# dual-dac-w-32-ch-sh-SH-BOARD_v2.net
KiCad netlist of a schematic drawn in EAGLE
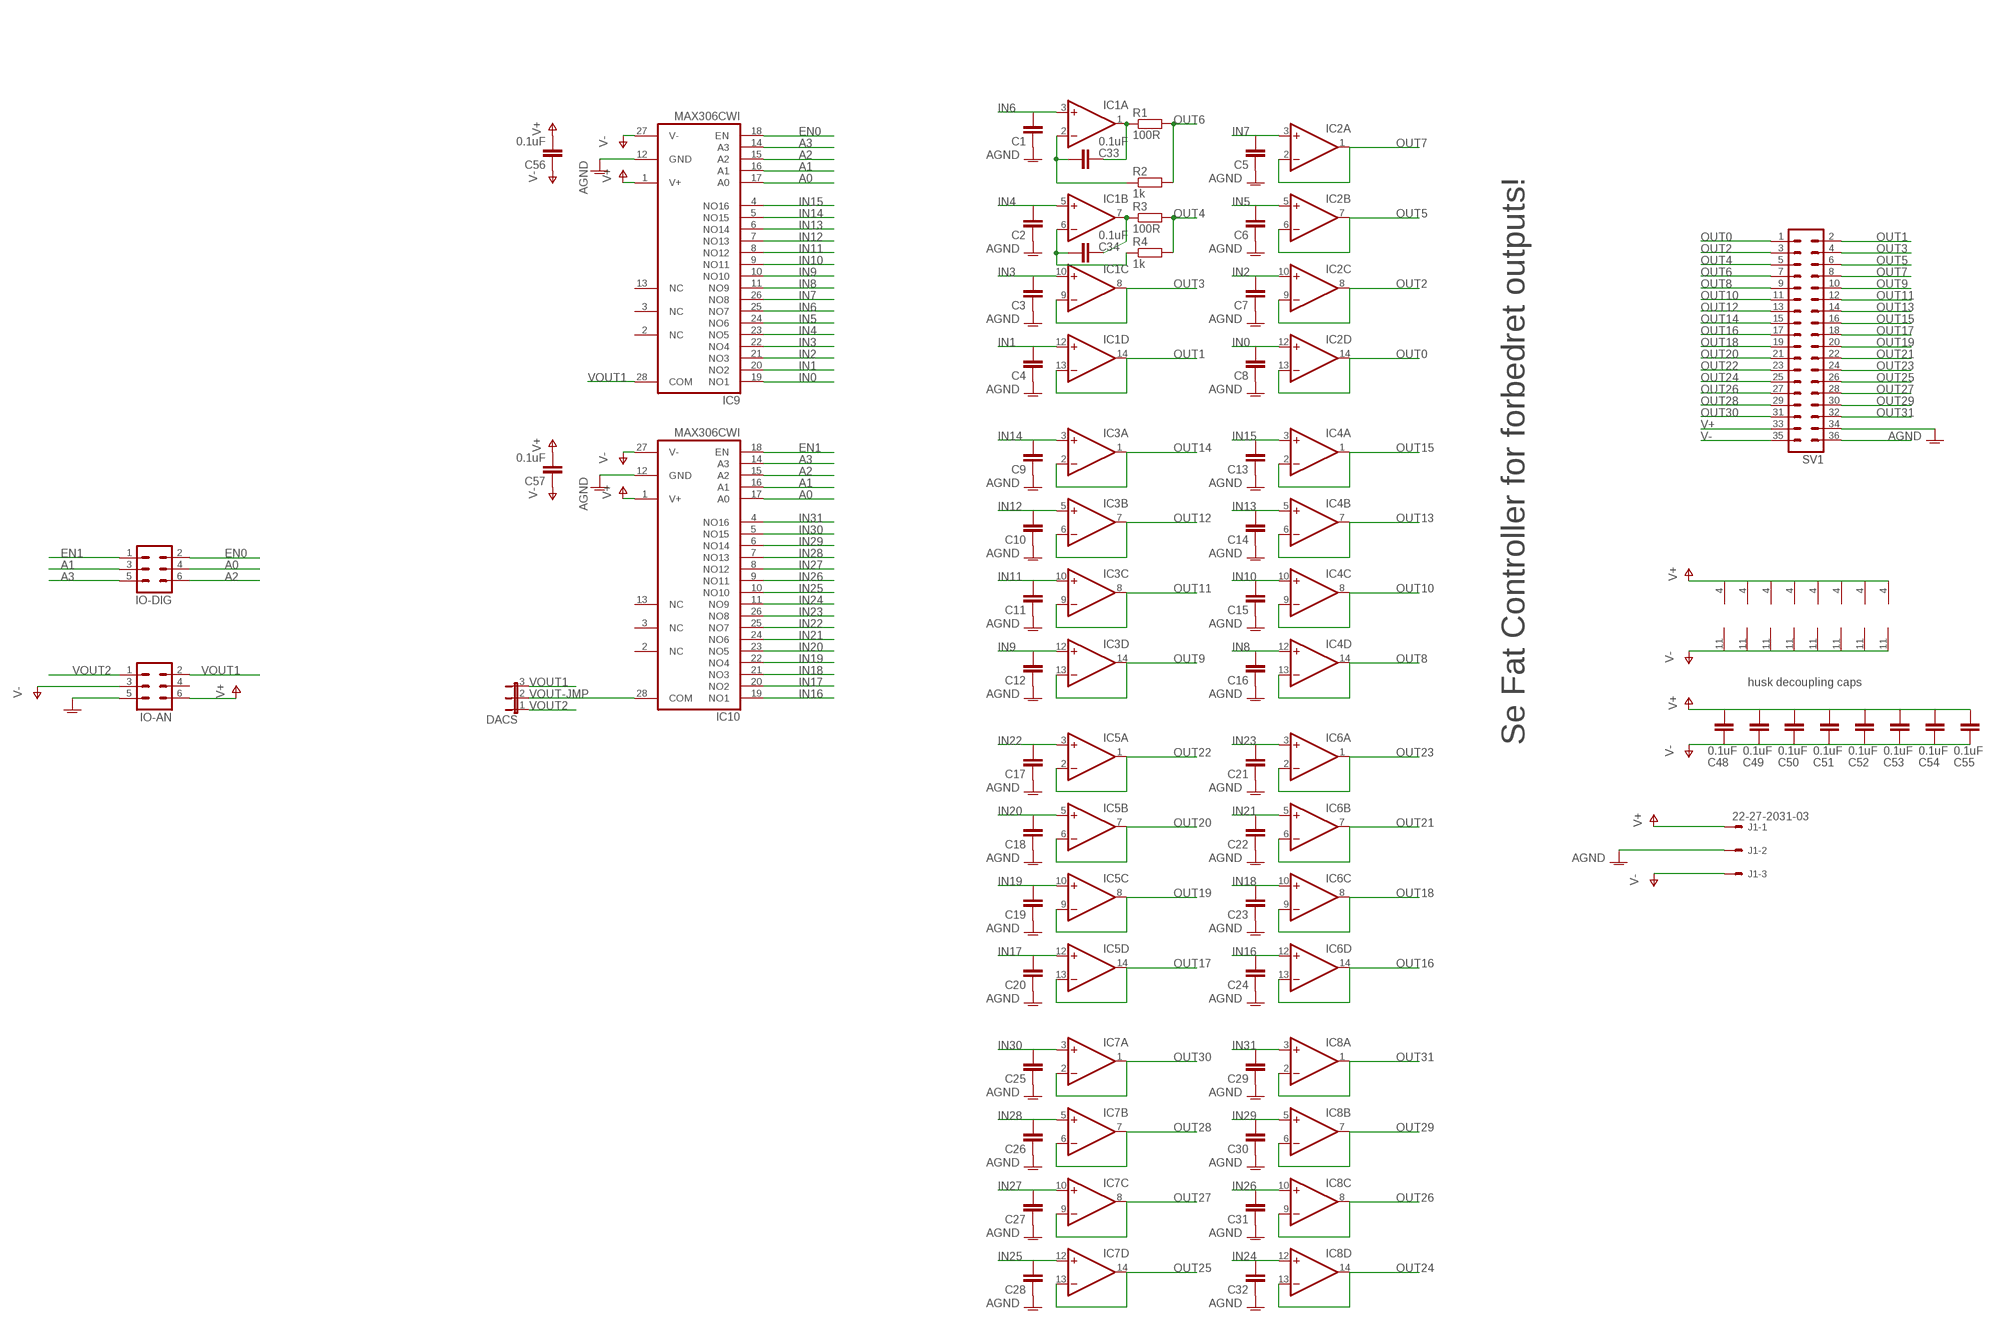
[diagram p0: schematic, sheet 1]

(export (version "E")
  (design (tool "Eeschema 10.0.6"))
  (components
    (comp (ref "C1")
      (value "C-EUC1206")
      (footprint "eagle-import:C1206")
      (libsource (lib "eagle-import") (part "C-EUC1206"))
    )
    (comp (ref "C2")
      (value "C-EUC1206")
      (footprint "eagle-import:C1206")
      (libsource (lib "eagle-import") (part "C-EUC1206"))
    )
    (comp (ref "C3")
      (value "C-EUC1206")
      (footprint "eagle-import:C1206")
      (libsource (lib "eagle-import") (part "C-EUC1206"))
    )
    (comp (ref "C4")
      (value "C-EUC1206")
      (footprint "eagle-import:C1206")
      (libsource (lib "eagle-import") (part "C-EUC1206"))
    )
    (comp (ref "C5")
      (value "C-EUC1206")
      (footprint "eagle-import:C1206")
      (libsource (lib "eagle-import") (part "C-EUC1206"))
    )
    (comp (ref "C6")
      (value "C-EUC1206")
      (footprint "eagle-import:C1206")
      (libsource (lib "eagle-import") (part "C-EUC1206"))
    )
    (comp (ref "C7")
      (value "C-EUC1206")
      (footprint "eagle-import:C1206")
      (libsource (lib "eagle-import") (part "C-EUC1206"))
    )
    (comp (ref "C8")
      (value "C-EUC1206")
      (footprint "eagle-import:C1206")
      (libsource (lib "eagle-import") (part "C-EUC1206"))
    )
    (comp (ref "C9")
      (value "C-EUC1206")
      (footprint "eagle-import:C1206")
      (libsource (lib "eagle-import") (part "C-EUC1206"))
    )
    (comp (ref "C10")
      (value "C-EUC1206")
      (footprint "eagle-import:C1206")
      (libsource (lib "eagle-import") (part "C-EUC1206"))
    )
    (comp (ref "C11")
      (value "C-EUC1206")
      (footprint "eagle-import:C1206")
      (libsource (lib "eagle-import") (part "C-EUC1206"))
    )
    (comp (ref "C12")
      (value "C-EUC1206")
      (footprint "eagle-import:C1206")
      (libsource (lib "eagle-import") (part "C-EUC1206"))
    )
    (comp (ref "C13")
      (value "C-EUC1206")
      (footprint "eagle-import:C1206")
      (libsource (lib "eagle-import") (part "C-EUC1206"))
    )
    (comp (ref "C14")
      (value "C-EUC1206")
      (footprint "eagle-import:C1206")
      (libsource (lib "eagle-import") (part "C-EUC1206"))
    )
    (comp (ref "C15")
      (value "C-EUC1206")
      (footprint "eagle-import:C1206")
      (libsource (lib "eagle-import") (part "C-EUC1206"))
    )
    (comp (ref "C16")
      (value "C-EUC1206")
      (footprint "eagle-import:C1206")
      (libsource (lib "eagle-import") (part "C-EUC1206"))
    )
    (comp (ref "C17")
      (value "C-EUC1206")
      (footprint "eagle-import:C1206")
      (libsource (lib "eagle-import") (part "C-EUC1206"))
    )
    (comp (ref "C18")
      (value "C-EUC1206")
      (footprint "eagle-import:C1206")
      (libsource (lib "eagle-import") (part "C-EUC1206"))
    )
    (comp (ref "C19")
      (value "C-EUC1206")
      (footprint "eagle-import:C1206")
      (libsource (lib "eagle-import") (part "C-EUC1206"))
    )
    (comp (ref "C20")
      (value "C-EUC1206")
      (footprint "eagle-import:C1206")
      (libsource (lib "eagle-import") (part "C-EUC1206"))
    )
    (comp (ref "C21")
      (value "C-EUC1206")
      (footprint "eagle-import:C1206")
      (libsource (lib "eagle-import") (part "C-EUC1206"))
    )
    (comp (ref "C22")
      (value "C-EUC1206")
      (footprint "eagle-import:C1206")
      (libsource (lib "eagle-import") (part "C-EUC1206"))
    )
    (comp (ref "C23")
      (value "C-EUC1206")
      (footprint "eagle-import:C1206")
      (libsource (lib "eagle-import") (part "C-EUC1206"))
    )
    (comp (ref "C24")
      (value "C-EUC1206")
      (footprint "eagle-import:C1206")
      (libsource (lib "eagle-import") (part "C-EUC1206"))
    )
    (comp (ref "C25")
      (value "C-EUC1206")
      (footprint "eagle-import:C1206")
      (libsource (lib "eagle-import") (part "C-EUC1206"))
    )
    (comp (ref "C26")
      (value "C-EUC1206")
      (footprint "eagle-import:C1206")
      (libsource (lib "eagle-import") (part "C-EUC1206"))
    )
    (comp (ref "C27")
      (value "C-EUC1206")
      (footprint "eagle-import:C1206")
      (libsource (lib "eagle-import") (part "C-EUC1206"))
    )
    (comp (ref "C28")
      (value "C-EUC1206")
      (footprint "eagle-import:C1206")
      (libsource (lib "eagle-import") (part "C-EUC1206"))
    )
    (comp (ref "C29")
      (value "C-EUC1206")
      (footprint "eagle-import:C1206")
      (libsource (lib "eagle-import") (part "C-EUC1206"))
    )
    (comp (ref "C30")
      (value "C-EUC1206")
      (footprint "eagle-import:C1206")
      (libsource (lib "eagle-import") (part "C-EUC1206"))
    )
    (comp (ref "C31")
      (value "C-EUC1206")
      (footprint "eagle-import:C1206")
      (libsource (lib "eagle-import") (part "C-EUC1206"))
    )
    (comp (ref "C32")
      (value "C-EUC1206")
      (footprint "eagle-import:C1206")
      (libsource (lib "eagle-import") (part "C-EUC1206"))
    )
    (comp (ref "C33")
      (value "0.1uF")
      (footprint "eagle-import:C0603")
      (libsource (lib "eagle-import") (part "C-EUC0603"))
    )
    (comp (ref "C34")
      (value "0.1uF")
      (footprint "eagle-import:C0603")
      (libsource (lib "eagle-import") (part "C-EUC0603"))
    )
    (comp (ref "C48")
      (value "0.1uF")
      (footprint "eagle-import:C0603")
      (libsource (lib "eagle-import") (part "C-EUC0603"))
    )
    (comp (ref "C49")
      (value "0.1uF")
      (footprint "eagle-import:C0603")
      (libsource (lib "eagle-import") (part "C-EUC0603"))
    )
    (comp (ref "C50")
      (value "0.1uF")
      (footprint "eagle-import:C0603")
      (libsource (lib "eagle-import") (part "C-EUC0603"))
    )
    (comp (ref "C51")
      (value "0.1uF")
      (footprint "eagle-import:C0603")
      (libsource (lib "eagle-import") (part "C-EUC0603"))
    )
    (comp (ref "C52")
      (value "0.1uF")
      (footprint "eagle-import:C0603")
      (libsource (lib "eagle-import") (part "C-EUC0603"))
    )
    (comp (ref "C53")
      (value "0.1uF")
      (footprint "eagle-import:C0603")
      (libsource (lib "eagle-import") (part "C-EUC0603"))
    )
    (comp (ref "C54")
      (value "0.1uF")
      (footprint "eagle-import:C0603")
      (libsource (lib "eagle-import") (part "C-EUC0603"))
    )
    (comp (ref "C55")
      (value "0.1uF")
      (footprint "eagle-import:C0603")
      (libsource (lib "eagle-import") (part "C-EUC0603"))
    )
    (comp (ref "C56")
      (value "0.1uF")
      (footprint "eagle-import:C0603")
      (libsource (lib "eagle-import") (part "C-EUC0603"))
    )
    (comp (ref "C57")
      (value "0.1uF")
      (footprint "eagle-import:C0603")
      (libsource (lib "eagle-import") (part "C-EUC0603"))
    )
    (comp (ref "DACS")
      (value "JP2E")
      (footprint "eagle-import:JP2")
      (libsource (lib "eagle-import") (part "JP2E"))
    )
    (comp (ref "IC1")
      (value "TL074D")
      (footprint "eagle-import:SO14")
      (libsource (lib "eagle-import") (part "TL074D"))
    )
    (comp (ref "IC2")
      (value "TL074D")
      (footprint "eagle-import:SO14")
      (libsource (lib "eagle-import") (part "TL074D"))
    )
    (comp (ref "IC3")
      (value "TL074D")
      (footprint "eagle-import:SO14")
      (libsource (lib "eagle-import") (part "TL074D"))
    )
    (comp (ref "IC4")
      (value "TL074D")
      (footprint "eagle-import:SO14")
      (libsource (lib "eagle-import") (part "TL074D"))
    )
    (comp (ref "IC5")
      (value "TL074D")
      (footprint "eagle-import:SO14")
      (libsource (lib "eagle-import") (part "TL074D"))
    )
    (comp (ref "IC6")
      (value "TL074D")
      (footprint "eagle-import:SO14")
      (libsource (lib "eagle-import") (part "TL074D"))
    )
    (comp (ref "IC7")
      (value "TL074D")
      (footprint "eagle-import:SO14")
      (libsource (lib "eagle-import") (part "TL074D"))
    )
    (comp (ref "IC8")
      (value "TL074D")
      (footprint "eagle-import:SO14")
      (libsource (lib "eagle-import") (part "TL074D"))
    )
    (comp (ref "IC9")
      (value "MAX306CWI")
      (footprint "eagle-import:SO28L")
      (fields (field (name "MF") "MAXIM"))
      (libsource (lib "eagle-import") (part "MAX306CWI"))
    )
    (comp (ref "IC10")
      (value "MAX306CWI")
      (footprint "eagle-import:SO28L")
      (fields (field (name "MF") "MAXIM"))
      (libsource (lib "eagle-import") (part "MAX306CWI"))
    )
    (comp (ref "IO-AN")
      (value "MA03-2")
      (footprint "eagle-import:MA03-2")
      (libsource (lib "eagle-import") (part "MA03-2"))
    )
    (comp (ref "IO-DIG")
      (value "MA03-2")
      (footprint "eagle-import:MA03-2")
      (libsource (lib "eagle-import") (part "MA03-2"))
    )
    (comp (ref "J1")
      (value "22-27-2031-03")
      (footprint "eagle-import:6410-03")
      (libsource (lib "eagle-import") (part "22-?-0327-2031"))
    )
    (comp (ref "R1")
      (value "100R")
      (footprint "eagle-import:R0603")
      (libsource (lib "eagle-import") (part "R-EU_R0603"))
    )
    (comp (ref "R2")
      (value "1k")
      (footprint "eagle-import:R0603")
      (libsource (lib "eagle-import") (part "R-EU_R0603"))
    )
    (comp (ref "R3")
      (value "100R")
      (footprint "eagle-import:R0603")
      (libsource (lib "eagle-import") (part "R-EU_R0603"))
    )
    (comp (ref "R4")
      (value "1k")
      (footprint "eagle-import:R0603")
      (libsource (lib "eagle-import") (part "R-EU_R0603"))
    )
    (comp (ref "SV1")
      (value "MA18-2")
      (footprint "eagle-import:MA18-2")
      (libsource (lib "eagle-import") (part "MA18-2"))
    )
  )
  (nets
    (net (code "1") (name "/A0") (class "Default")
      (node (ref "IC10") (pin "17") (pinfunction "A0_17") (pintype "input"))
      (node (ref "IC9") (pin "17") (pinfunction "A0_17") (pintype "input"))
      (node (ref "IO-DIG") (pin "4") (pinfunction "4_4") (pintype "passive"))
    )
    (net (code "2") (name "/A1") (class "Default")
      (node (ref "IC10") (pin "16") (pinfunction "A1_16") (pintype "input"))
      (node (ref "IC9") (pin "16") (pinfunction "A1_16") (pintype "input"))
      (node (ref "IO-DIG") (pin "3") (pinfunction "3_3") (pintype "passive"))
    )
    (net (code "3") (name "/A2") (class "Default")
      (node (ref "IC10") (pin "15") (pinfunction "A2_15") (pintype "input"))
      (node (ref "IC9") (pin "15") (pinfunction "A2_15") (pintype "input"))
      (node (ref "IO-DIG") (pin "6") (pinfunction "6_6") (pintype "passive"))
    )
    (net (code "4") (name "/A3") (class "Default")
      (node (ref "IC10") (pin "14") (pinfunction "A3_14") (pintype "input"))
      (node (ref "IC9") (pin "14") (pinfunction "A3_14") (pintype "input"))
      (node (ref "IO-DIG") (pin "5") (pinfunction "5_5") (pintype "passive"))
    )
    (net (code "5") (name "/EN0") (class "Default")
      (node (ref "IC9") (pin "18") (pinfunction "EN_18") (pintype "input"))
      (node (ref "IO-DIG") (pin "2") (pinfunction "2_2") (pintype "passive"))
    )
    (net (code "6") (name "/EN1") (class "Default")
      (node (ref "IC10") (pin "18") (pinfunction "EN_18") (pintype "input"))
      (node (ref "IO-DIG") (pin "1") (pinfunction "1_1") (pintype "passive"))
    )
    (net (code "7") (name "/IN0") (class "Default")
      (node (ref "C8") (pin "2") (pinfunction "2_2") (pintype "passive"))
      (node (ref "IC2") (pin "12") (pinfunction "+IN_12") (pintype "input"))
      (node (ref "IC9") (pin "19") (pinfunction "NO1_19") (pintype "passive"))
    )
    (net (code "8") (name "/IN1") (class "Default")
      (node (ref "C4") (pin "2") (pinfunction "2_2") (pintype "passive"))
      (node (ref "IC1") (pin "12") (pinfunction "+IN_12") (pintype "input"))
      (node (ref "IC9") (pin "20") (pinfunction "NO2_20") (pintype "passive"))
    )
    (net (code "9") (name "/IN2") (class "Default")
      (node (ref "C7") (pin "2") (pinfunction "2_2") (pintype "passive"))
      (node (ref "IC2") (pin "10") (pinfunction "+IN_10") (pintype "input"))
      (node (ref "IC9") (pin "21") (pinfunction "NO3_21") (pintype "passive"))
    )
    (net (code "10") (name "/IN3") (class "Default")
      (node (ref "C3") (pin "2") (pinfunction "2_2") (pintype "passive"))
      (node (ref "IC1") (pin "10") (pinfunction "+IN_10") (pintype "input"))
      (node (ref "IC9") (pin "22") (pinfunction "NO4_22") (pintype "passive"))
    )
    (net (code "11") (name "/IN4") (class "Default")
      (node (ref "C2") (pin "2") (pinfunction "2_2") (pintype "passive"))
      (node (ref "IC1") (pin "5") (pinfunction "+IN_5") (pintype "input"))
      (node (ref "IC9") (pin "23") (pinfunction "NO5_23") (pintype "passive"))
    )
    (net (code "12") (name "/IN5") (class "Default")
      (node (ref "C6") (pin "2") (pinfunction "2_2") (pintype "passive"))
      (node (ref "IC2") (pin "5") (pinfunction "+IN_5") (pintype "input"))
      (node (ref "IC9") (pin "24") (pinfunction "NO6_24") (pintype "passive"))
    )
    (net (code "13") (name "/IN6") (class "Default")
      (node (ref "C1") (pin "2") (pinfunction "2_2") (pintype "passive"))
      (node (ref "IC1") (pin "3") (pinfunction "+IN_3") (pintype "input"))
      (node (ref "IC9") (pin "25") (pinfunction "NO7_25") (pintype "passive"))
    )
    (net (code "14") (name "/IN7") (class "Default")
      (node (ref "C5") (pin "2") (pinfunction "2_2") (pintype "passive"))
      (node (ref "IC2") (pin "3") (pinfunction "+IN_3") (pintype "input"))
      (node (ref "IC9") (pin "26") (pinfunction "NO8_26") (pintype "passive"))
    )
    (net (code "15") (name "/IN8") (class "Default")
      (node (ref "C16") (pin "2") (pinfunction "2_2") (pintype "passive"))
      (node (ref "IC4") (pin "12") (pinfunction "+IN_12") (pintype "input"))
      (node (ref "IC9") (pin "11") (pinfunction "NO9_11") (pintype "passive"))
    )
    (net (code "16") (name "/IN9") (class "Default")
      (node (ref "C12") (pin "2") (pinfunction "2_2") (pintype "passive"))
      (node (ref "IC3") (pin "12") (pinfunction "+IN_12") (pintype "input"))
      (node (ref "IC9") (pin "10") (pinfunction "NO10_10") (pintype "passive"))
    )
    (net (code "17") (name "/IN10") (class "Default")
      (node (ref "C15") (pin "2") (pinfunction "2_2") (pintype "passive"))
      (node (ref "IC4") (pin "10") (pinfunction "+IN_10") (pintype "input"))
      (node (ref "IC9") (pin "9") (pinfunction "NO11_9") (pintype "passive"))
    )
    (net (code "18") (name "/IN11") (class "Default")
      (node (ref "C11") (pin "2") (pinfunction "2_2") (pintype "passive"))
      (node (ref "IC3") (pin "10") (pinfunction "+IN_10") (pintype "input"))
      (node (ref "IC9") (pin "8") (pinfunction "NO12_8") (pintype "passive"))
    )
    (net (code "19") (name "/IN12") (class "Default")
      (node (ref "C10") (pin "2") (pinfunction "2_2") (pintype "passive"))
      (node (ref "IC3") (pin "5") (pinfunction "+IN_5") (pintype "input"))
      (node (ref "IC9") (pin "7") (pinfunction "NO13_7") (pintype "passive"))
    )
    (net (code "20") (name "/IN13") (class "Default")
      (node (ref "C14") (pin "2") (pinfunction "2_2") (pintype "passive"))
      (node (ref "IC4") (pin "5") (pinfunction "+IN_5") (pintype "input"))
      (node (ref "IC9") (pin "6") (pinfunction "NO14_6") (pintype "passive"))
    )
    (net (code "21") (name "/IN14") (class "Default")
      (node (ref "C9") (pin "2") (pinfunction "2_2") (pintype "passive"))
      (node (ref "IC3") (pin "3") (pinfunction "+IN_3") (pintype "input"))
      (node (ref "IC9") (pin "5") (pinfunction "NO15_5") (pintype "passive"))
    )
    (net (code "22") (name "/IN15") (class "Default")
      (node (ref "C13") (pin "2") (pinfunction "2_2") (pintype "passive"))
      (node (ref "IC4") (pin "3") (pinfunction "+IN_3") (pintype "input"))
      (node (ref "IC9") (pin "4") (pinfunction "NO16_4") (pintype "passive"))
    )
    (net (code "23") (name "/IN16") (class "Default")
      (node (ref "C24") (pin "2") (pinfunction "2_2") (pintype "passive"))
      (node (ref "IC10") (pin "19") (pinfunction "NO1_19") (pintype "passive"))
      (node (ref "IC6") (pin "12") (pinfunction "+IN_12") (pintype "input"))
    )
    (net (code "24") (name "/IN17") (class "Default")
      (node (ref "C20") (pin "2") (pinfunction "2_2") (pintype "passive"))
      (node (ref "IC10") (pin "20") (pinfunction "NO2_20") (pintype "passive"))
      (node (ref "IC5") (pin "12") (pinfunction "+IN_12") (pintype "input"))
    )
    (net (code "25") (name "/IN18") (class "Default")
      (node (ref "C23") (pin "2") (pinfunction "2_2") (pintype "passive"))
      (node (ref "IC10") (pin "21") (pinfunction "NO3_21") (pintype "passive"))
      (node (ref "IC6") (pin "10") (pinfunction "+IN_10") (pintype "input"))
    )
    (net (code "26") (name "/IN19") (class "Default")
      (node (ref "C19") (pin "2") (pinfunction "2_2") (pintype "passive"))
      (node (ref "IC10") (pin "22") (pinfunction "NO4_22") (pintype "passive"))
      (node (ref "IC5") (pin "10") (pinfunction "+IN_10") (pintype "input"))
    )
    (net (code "27") (name "/IN20") (class "Default")
      (node (ref "C18") (pin "2") (pinfunction "2_2") (pintype "passive"))
      (node (ref "IC10") (pin "23") (pinfunction "NO5_23") (pintype "passive"))
      (node (ref "IC5") (pin "5") (pinfunction "+IN_5") (pintype "input"))
    )
    (net (code "28") (name "/IN21") (class "Default")
      (node (ref "C22") (pin "2") (pinfunction "2_2") (pintype "passive"))
      (node (ref "IC10") (pin "24") (pinfunction "NO6_24") (pintype "passive"))
      (node (ref "IC6") (pin "5") (pinfunction "+IN_5") (pintype "input"))
    )
    (net (code "29") (name "/IN22") (class "Default")
      (node (ref "C17") (pin "2") (pinfunction "2_2") (pintype "passive"))
      (node (ref "IC10") (pin "25") (pinfunction "NO7_25") (pintype "passive"))
      (node (ref "IC5") (pin "3") (pinfunction "+IN_3") (pintype "input"))
    )
    (net (code "30") (name "/IN23") (class "Default")
      (node (ref "C21") (pin "2") (pinfunction "2_2") (pintype "passive"))
      (node (ref "IC10") (pin "26") (pinfunction "NO8_26") (pintype "passive"))
      (node (ref "IC6") (pin "3") (pinfunction "+IN_3") (pintype "input"))
    )
    (net (code "31") (name "/IN24") (class "Default")
      (node (ref "C32") (pin "2") (pinfunction "2_2") (pintype "passive"))
      (node (ref "IC10") (pin "11") (pinfunction "NO9_11") (pintype "passive"))
      (node (ref "IC8") (pin "12") (pinfunction "+IN_12") (pintype "input"))
    )
    (net (code "32") (name "/IN25") (class "Default")
      (node (ref "C28") (pin "2") (pinfunction "2_2") (pintype "passive"))
      (node (ref "IC10") (pin "10") (pinfunction "NO10_10") (pintype "passive"))
      (node (ref "IC7") (pin "12") (pinfunction "+IN_12") (pintype "input"))
    )
    (net (code "33") (name "/IN26") (class "Default")
      (node (ref "C31") (pin "2") (pinfunction "2_2") (pintype "passive"))
      (node (ref "IC10") (pin "9") (pinfunction "NO11_9") (pintype "passive"))
      (node (ref "IC8") (pin "10") (pinfunction "+IN_10") (pintype "input"))
    )
    (net (code "34") (name "/IN27") (class "Default")
      (node (ref "C27") (pin "2") (pinfunction "2_2") (pintype "passive"))
      (node (ref "IC10") (pin "8") (pinfunction "NO12_8") (pintype "passive"))
      (node (ref "IC7") (pin "10") (pinfunction "+IN_10") (pintype "input"))
    )
    (net (code "35") (name "/IN28") (class "Default")
      (node (ref "C26") (pin "2") (pinfunction "2_2") (pintype "passive"))
      (node (ref "IC10") (pin "7") (pinfunction "NO13_7") (pintype "passive"))
      (node (ref "IC7") (pin "5") (pinfunction "+IN_5") (pintype "input"))
    )
    (net (code "36") (name "/IN29") (class "Default")
      (node (ref "C30") (pin "2") (pinfunction "2_2") (pintype "passive"))
      (node (ref "IC10") (pin "6") (pinfunction "NO14_6") (pintype "passive"))
      (node (ref "IC8") (pin "5") (pinfunction "+IN_5") (pintype "input"))
    )
    (net (code "37") (name "/IN30") (class "Default")
      (node (ref "C25") (pin "2") (pinfunction "2_2") (pintype "passive"))
      (node (ref "IC10") (pin "5") (pinfunction "NO15_5") (pintype "passive"))
      (node (ref "IC7") (pin "3") (pinfunction "+IN_3") (pintype "input"))
    )
    (net (code "38") (name "/IN31") (class "Default")
      (node (ref "C29") (pin "2") (pinfunction "2_2") (pintype "passive"))
      (node (ref "IC10") (pin "4") (pinfunction "NO16_4") (pintype "passive"))
      (node (ref "IC8") (pin "3") (pinfunction "+IN_3") (pintype "input"))
    )
    (net (code "39") (name "/OUT0") (class "Default")
      (node (ref "IC2") (pin "13") (pinfunction "-IN_13") (pintype "input"))
      (node (ref "IC2") (pin "14") (pinfunction "OUT_14") (pintype "output"))
      (node (ref "SV1") (pin "1") (pinfunction "1_1") (pintype "passive"))
    )
    (net (code "40") (name "/OUT1") (class "Default")
      (node (ref "IC1") (pin "13") (pinfunction "-IN_13") (pintype "input"))
      (node (ref "IC1") (pin "14") (pinfunction "OUT_14") (pintype "output"))
      (node (ref "SV1") (pin "2") (pinfunction "2_2") (pintype "passive"))
    )
    (net (code "41") (name "/OUT2") (class "Default")
      (node (ref "IC2") (pin "8") (pinfunction "OUT_8") (pintype "output"))
      (node (ref "IC2") (pin "9") (pinfunction "-IN_9") (pintype "input"))
      (node (ref "SV1") (pin "3") (pinfunction "3_3") (pintype "passive"))
    )
    (net (code "42") (name "/OUT3") (class "Default")
      (node (ref "IC1") (pin "8") (pinfunction "OUT_8") (pintype "output"))
      (node (ref "IC1") (pin "9") (pinfunction "-IN_9") (pintype "input"))
      (node (ref "SV1") (pin "4") (pinfunction "4_4") (pintype "passive"))
    )
    (net (code "43") (name "/OUT4") (class "Default")
      (node (ref "R3") (pin "2") (pinfunction "2_2") (pintype "passive"))
      (node (ref "R4") (pin "2") (pinfunction "2_2") (pintype "passive"))
      (node (ref "SV1") (pin "5") (pinfunction "5_5") (pintype "passive"))
    )
    (net (code "44") (name "/OUT5") (class "Default")
      (node (ref "IC2") (pin "6") (pinfunction "-IN_6") (pintype "input"))
      (node (ref "IC2") (pin "7") (pinfunction "OUT_7") (pintype "output"))
      (node (ref "SV1") (pin "6") (pinfunction "6_6") (pintype "passive"))
    )
    (net (code "45") (name "/OUT6") (class "Default")
      (node (ref "R1") (pin "2") (pinfunction "2_2") (pintype "passive"))
      (node (ref "R2") (pin "2") (pinfunction "2_2") (pintype "passive"))
      (node (ref "SV1") (pin "7") (pinfunction "7_7") (pintype "passive"))
    )
    (net (code "46") (name "/OUT7") (class "Default")
      (node (ref "IC2") (pin "1") (pinfunction "OUT_1") (pintype "output"))
      (node (ref "IC2") (pin "2") (pinfunction "-IN_2") (pintype "input"))
      (node (ref "SV1") (pin "8") (pinfunction "8_8") (pintype "passive"))
    )
    (net (code "47") (name "/OUT8") (class "Default")
      (node (ref "IC4") (pin "13") (pinfunction "-IN_13") (pintype "input"))
      (node (ref "IC4") (pin "14") (pinfunction "OUT_14") (pintype "output"))
      (node (ref "SV1") (pin "9") (pinfunction "9_9") (pintype "passive"))
    )
    (net (code "48") (name "/OUT9") (class "Default")
      (node (ref "IC3") (pin "13") (pinfunction "-IN_13") (pintype "input"))
      (node (ref "IC3") (pin "14") (pinfunction "OUT_14") (pintype "output"))
      (node (ref "SV1") (pin "10") (pinfunction "10_10") (pintype "passive"))
    )
    (net (code "49") (name "/OUT10") (class "Default")
      (node (ref "IC4") (pin "8") (pinfunction "OUT_8") (pintype "output"))
      (node (ref "IC4") (pin "9") (pinfunction "-IN_9") (pintype "input"))
      (node (ref "SV1") (pin "11") (pinfunction "11_11") (pintype "passive"))
    )
    (net (code "50") (name "/OUT11") (class "Default")
      (node (ref "IC3") (pin "8") (pinfunction "OUT_8") (pintype "output"))
      (node (ref "IC3") (pin "9") (pinfunction "-IN_9") (pintype "input"))
      (node (ref "SV1") (pin "12") (pinfunction "12_12") (pintype "passive"))
    )
    (net (code "51") (name "/OUT12") (class "Default")
      (node (ref "IC3") (pin "6") (pinfunction "-IN_6") (pintype "input"))
      (node (ref "IC3") (pin "7") (pinfunction "OUT_7") (pintype "output"))
      (node (ref "SV1") (pin "13") (pinfunction "13_13") (pintype "passive"))
    )
    (net (code "52") (name "/OUT13") (class "Default")
      (node (ref "IC4") (pin "6") (pinfunction "-IN_6") (pintype "input"))
      (node (ref "IC4") (pin "7") (pinfunction "OUT_7") (pintype "output"))
      (node (ref "SV1") (pin "14") (pinfunction "14_14") (pintype "passive"))
    )
    (net (code "53") (name "/OUT14") (class "Default")
      (node (ref "IC3") (pin "1") (pinfunction "OUT_1") (pintype "output"))
      (node (ref "IC3") (pin "2") (pinfunction "-IN_2") (pintype "input"))
      (node (ref "SV1") (pin "15") (pinfunction "15_15") (pintype "passive"))
    )
    (net (code "54") (name "/OUT15") (class "Default")
      (node (ref "IC4") (pin "1") (pinfunction "OUT_1") (pintype "output"))
      (node (ref "IC4") (pin "2") (pinfunction "-IN_2") (pintype "input"))
      (node (ref "SV1") (pin "16") (pinfunction "16_16") (pintype "passive"))
    )
    (net (code "55") (name "/OUT16") (class "Default")
      (node (ref "IC6") (pin "13") (pinfunction "-IN_13") (pintype "input"))
      (node (ref "IC6") (pin "14") (pinfunction "OUT_14") (pintype "output"))
      (node (ref "SV1") (pin "17") (pinfunction "17_17") (pintype "passive"))
    )
    (net (code "56") (name "/OUT17") (class "Default")
      (node (ref "IC5") (pin "13") (pinfunction "-IN_13") (pintype "input"))
      (node (ref "IC5") (pin "14") (pinfunction "OUT_14") (pintype "output"))
      (node (ref "SV1") (pin "18") (pinfunction "18_18") (pintype "passive"))
    )
    (net (code "57") (name "/OUT18") (class "Default")
      (node (ref "IC6") (pin "8") (pinfunction "OUT_8") (pintype "output"))
      (node (ref "IC6") (pin "9") (pinfunction "-IN_9") (pintype "input"))
      (node (ref "SV1") (pin "19") (pinfunction "19_19") (pintype "passive"))
    )
    (net (code "58") (name "/OUT19") (class "Default")
      (node (ref "IC5") (pin "8") (pinfunction "OUT_8") (pintype "output"))
      (node (ref "IC5") (pin "9") (pinfunction "-IN_9") (pintype "input"))
      (node (ref "SV1") (pin "20") (pinfunction "20_20") (pintype "passive"))
    )
    (net (code "59") (name "/OUT20") (class "Default")
      (node (ref "IC5") (pin "6") (pinfunction "-IN_6") (pintype "input"))
      (node (ref "IC5") (pin "7") (pinfunction "OUT_7") (pintype "output"))
      (node (ref "SV1") (pin "21") (pinfunction "21_21") (pintype "passive"))
    )
    (net (code "60") (name "/OUT21") (class "Default")
      (node (ref "IC6") (pin "6") (pinfunction "-IN_6") (pintype "input"))
      (node (ref "IC6") (pin "7") (pinfunction "OUT_7") (pintype "output"))
      (node (ref "SV1") (pin "22") (pinfunction "22_22") (pintype "passive"))
    )
    (net (code "61") (name "/OUT22") (class "Default")
      (node (ref "IC5") (pin "1") (pinfunction "OUT_1") (pintype "output"))
      (node (ref "IC5") (pin "2") (pinfunction "-IN_2") (pintype "input"))
      (node (ref "SV1") (pin "23") (pinfunction "23_23") (pintype "passive"))
    )
    (net (code "62") (name "/OUT23") (class "Default")
      (node (ref "IC6") (pin "1") (pinfunction "OUT_1") (pintype "output"))
      (node (ref "IC6") (pin "2") (pinfunction "-IN_2") (pintype "input"))
      (node (ref "SV1") (pin "24") (pinfunction "24_24") (pintype "passive"))
    )
    (net (code "63") (name "/OUT24") (class "Default")
      (node (ref "IC8") (pin "13") (pinfunction "-IN_13") (pintype "input"))
      (node (ref "IC8") (pin "14") (pinfunction "OUT_14") (pintype "output"))
      (node (ref "SV1") (pin "25") (pinfunction "25_25") (pintype "passive"))
    )
    (net (code "64") (name "/OUT25") (class "Default")
      (node (ref "IC7") (pin "13") (pinfunction "-IN_13") (pintype "input"))
      (node (ref "IC7") (pin "14") (pinfunction "OUT_14") (pintype "output"))
      (node (ref "SV1") (pin "26") (pinfunction "26_26") (pintype "passive"))
    )
    (net (code "65") (name "/OUT26") (class "Default")
      (node (ref "IC8") (pin "8") (pinfunction "OUT_8") (pintype "output"))
      (node (ref "IC8") (pin "9") (pinfunction "-IN_9") (pintype "input"))
      (node (ref "SV1") (pin "27") (pinfunction "27_27") (pintype "passive"))
    )
    (net (code "66") (name "/OUT27") (class "Default")
      (node (ref "IC7") (pin "8") (pinfunction "OUT_8") (pintype "output"))
      (node (ref "IC7") (pin "9") (pinfunction "-IN_9") (pintype "input"))
      (node (ref "SV1") (pin "28") (pinfunction "28_28") (pintype "passive"))
    )
    (net (code "67") (name "/OUT28") (class "Default")
      (node (ref "IC7") (pin "6") (pinfunction "-IN_6") (pintype "input"))
      (node (ref "IC7") (pin "7") (pinfunction "OUT_7") (pintype "output"))
      (node (ref "SV1") (pin "29") (pinfunction "29_29") (pintype "passive"))
    )
    (net (code "68") (name "/OUT29") (class "Default")
      (node (ref "IC8") (pin "6") (pinfunction "-IN_6") (pintype "input"))
      (node (ref "IC8") (pin "7") (pinfunction "OUT_7") (pintype "output"))
      (node (ref "SV1") (pin "30") (pinfunction "30_30") (pintype "passive"))
    )
    (net (code "69") (name "/OUT30") (class "Default")
      (node (ref "IC7") (pin "1") (pinfunction "OUT_1") (pintype "output"))
      (node (ref "IC7") (pin "2") (pinfunction "-IN_2") (pintype "input"))
      (node (ref "SV1") (pin "31") (pinfunction "31_31") (pintype "passive"))
    )
    (net (code "70") (name "/OUT31") (class "Default")
      (node (ref "IC8") (pin "1") (pinfunction "OUT_1") (pintype "output"))
      (node (ref "IC8") (pin "2") (pinfunction "-IN_2") (pintype "input"))
      (node (ref "SV1") (pin "32") (pinfunction "32_32") (pintype "passive"))
    )
    (net (code "71") (name "/VOUT-JMP") (class "Default")
      (node (ref "DACS") (pin "2") (pinfunction "2_2") (pintype "passive"))
      (node (ref "IC10") (pin "28") (pinfunction "COM_28") (pintype "passive"))
    )
    (net (code "72") (name "/VOUT1") (class "Default")
      (node (ref "DACS") (pin "3") (pinfunction "3_3") (pintype "passive"))
      (node (ref "IC9") (pin "28") (pinfunction "COM_28") (pintype "passive"))
      (node (ref "IO-AN") (pin "2") (pinfunction "2_2") (pintype "passive"))
    )
    (net (code "73") (name "/VOUT2") (class "Default")
      (node (ref "DACS") (pin "1") (pinfunction "1_1") (pintype "passive"))
      (node (ref "IO-AN") (pin "1") (pinfunction "1_1") (pintype "passive"))
    )
    (net (code "74") (name "AGND") (class "Default")
      (node (ref "C1") (pin "1") (pinfunction "1_1") (pintype "passive"))
      (node (ref "C10") (pin "1") (pinfunction "1_1") (pintype "passive"))
      (node (ref "C11") (pin "1") (pinfunction "1_1") (pintype "passive"))
      (node (ref "C12") (pin "1") (pinfunction "1_1") (pintype "passive"))
      (node (ref "C13") (pin "1") (pinfunction "1_1") (pintype "passive"))
      (node (ref "C14") (pin "1") (pinfunction "1_1") (pintype "passive"))
      (node (ref "C15") (pin "1") (pinfunction "1_1") (pintype "passive"))
      (node (ref "C16") (pin "1") (pinfunction "1_1") (pintype "passive"))
      (node (ref "C17") (pin "1") (pinfunction "1_1") (pintype "passive"))
      (node (ref "C18") (pin "1") (pinfunction "1_1") (pintype "passive"))
      (node (ref "C19") (pin "1") (pinfunction "1_1") (pintype "passive"))
      (node (ref "C2") (pin "1") (pinfunction "1_1") (pintype "passive"))
      (node (ref "C20") (pin "1") (pinfunction "1_1") (pintype "passive"))
      (node (ref "C21") (pin "1") (pinfunction "1_1") (pintype "passive"))
      (node (ref "C22") (pin "1") (pinfunction "1_1") (pintype "passive"))
      (node (ref "C23") (pin "1") (pinfunction "1_1") (pintype "passive"))
      (node (ref "C24") (pin "1") (pinfunction "1_1") (pintype "passive"))
      (node (ref "C25") (pin "1") (pinfunction "1_1") (pintype "passive"))
      (node (ref "C26") (pin "1") (pinfunction "1_1") (pintype "passive"))
      (node (ref "C27") (pin "1") (pinfunction "1_1") (pintype "passive"))
      (node (ref "C28") (pin "1") (pinfunction "1_1") (pintype "passive"))
      (node (ref "C29") (pin "1") (pinfunction "1_1") (pintype "passive"))
      (node (ref "C3") (pin "1") (pinfunction "1_1") (pintype "passive"))
      (node (ref "C30") (pin "1") (pinfunction "1_1") (pintype "passive"))
      (node (ref "C31") (pin "1") (pinfunction "1_1") (pintype "passive"))
      (node (ref "C32") (pin "1") (pinfunction "1_1") (pintype "passive"))
      (node (ref "C4") (pin "1") (pinfunction "1_1") (pintype "passive"))
      (node (ref "C5") (pin "1") (pinfunction "1_1") (pintype "passive"))
      (node (ref "C6") (pin "1") (pinfunction "1_1") (pintype "passive"))
      (node (ref "C7") (pin "1") (pinfunction "1_1") (pintype "passive"))
      (node (ref "C8") (pin "1") (pinfunction "1_1") (pintype "passive"))
      (node (ref "C9") (pin "1") (pinfunction "1_1") (pintype "passive"))
      (node (ref "IC10") (pin "12") (pinfunction "GND_12") (pintype "power_in"))
      (node (ref "IC9") (pin "12") (pinfunction "GND_12") (pintype "power_in"))
      (node (ref "IO-AN") (pin "5") (pinfunction "5_5") (pintype "passive"))
      (node (ref "J1") (pin "2") (pinfunction "S_2") (pintype "passive"))
      (node (ref "SV1") (pin "34") (pinfunction "34_34") (pintype "passive"))
    )
    (net (code "75") (name "Net-(IC1A--IN)") (class "Default")
      (node (ref "C33") (pin "2") (pinfunction "2_2") (pintype "passive"))
      (node (ref "IC1") (pin "2") (pinfunction "-IN_2") (pintype "input"))
      (node (ref "R2") (pin "1") (pinfunction "1_1") (pintype "passive"))
    )
    (net (code "76") (name "Net-(IC1A-OUT)") (class "Default")
      (node (ref "C33") (pin "1") (pinfunction "1_1") (pintype "passive"))
      (node (ref "IC1") (pin "1") (pinfunction "OUT_1") (pintype "output"))
      (node (ref "R1") (pin "1") (pinfunction "1_1") (pintype "passive"))
    )
    (net (code "77") (name "Net-(IC1B--IN)") (class "Default")
      (node (ref "C34") (pin "2") (pinfunction "2_2") (pintype "passive"))
      (node (ref "IC1") (pin "6") (pinfunction "-IN_6") (pintype "input"))
      (node (ref "R4") (pin "1") (pinfunction "1_1") (pintype "passive"))
    )
    (net (code "78") (name "Net-(IC1B-OUT)") (class "Default")
      (node (ref "C34") (pin "1") (pinfunction "1_1") (pintype "passive"))
      (node (ref "IC1") (pin "7") (pinfunction "OUT_7") (pintype "output"))
      (node (ref "R3") (pin "1") (pinfunction "1_1") (pintype "passive"))
    )
    (net (code "79") (name "V+") (class "Default")
      (node (ref "C48") (pin "2") (pinfunction "2_2") (pintype "passive"))
      (node (ref "C49") (pin "2") (pinfunction "2_2") (pintype "passive"))
      (node (ref "C50") (pin "2") (pinfunction "2_2") (pintype "passive"))
      (node (ref "C51") (pin "2") (pinfunction "2_2") (pintype "passive"))
      (node (ref "C52") (pin "2") (pinfunction "2_2") (pintype "passive"))
      (node (ref "C53") (pin "2") (pinfunction "2_2") (pintype "passive"))
      (node (ref "C54") (pin "2") (pinfunction "2_2") (pintype "passive"))
      (node (ref "C55") (pin "2") (pinfunction "2_2") (pintype "passive"))
      (node (ref "C56") (pin "2") (pinfunction "2_2") (pintype "passive"))
      (node (ref "C57") (pin "2") (pinfunction "2_2") (pintype "passive"))
      (node (ref "IC1") (pin "4") (pinfunction "V+_4") (pintype "power_in"))
      (node (ref "IC10") (pin "1") (pinfunction "V+_1") (pintype "power_in"))
      (node (ref "IC2") (pin "4") (pinfunction "V+_4") (pintype "power_in"))
      (node (ref "IC3") (pin "4") (pinfunction "V+_4") (pintype "power_in"))
      (node (ref "IC4") (pin "4") (pinfunction "V+_4") (pintype "power_in"))
      (node (ref "IC5") (pin "4") (pinfunction "V+_4") (pintype "power_in"))
      (node (ref "IC6") (pin "4") (pinfunction "V+_4") (pintype "power_in"))
      (node (ref "IC7") (pin "4") (pinfunction "V+_4") (pintype "power_in"))
      (node (ref "IC8") (pin "4") (pinfunction "V+_4") (pintype "power_in"))
      (node (ref "IC9") (pin "1") (pinfunction "V+_1") (pintype "power_in"))
      (node (ref "IO-AN") (pin "6") (pinfunction "6_6") (pintype "passive"))
      (node (ref "J1") (pin "1") (pinfunction "S_1") (pintype "passive"))
      (node (ref "SV1") (pin "33") (pinfunction "33_33") (pintype "passive"))
    )
    (net (code "80") (name "V-") (class "Default")
      (node (ref "C48") (pin "1") (pinfunction "1_1") (pintype "passive"))
      (node (ref "C49") (pin "1") (pinfunction "1_1") (pintype "passive"))
      (node (ref "C50") (pin "1") (pinfunction "1_1") (pintype "passive"))
      (node (ref "C51") (pin "1") (pinfunction "1_1") (pintype "passive"))
      (node (ref "C52") (pin "1") (pinfunction "1_1") (pintype "passive"))
      (node (ref "C53") (pin "1") (pinfunction "1_1") (pintype "passive"))
      (node (ref "C54") (pin "1") (pinfunction "1_1") (pintype "passive"))
      (node (ref "C55") (pin "1") (pinfunction "1_1") (pintype "passive"))
      (node (ref "C56") (pin "1") (pinfunction "1_1") (pintype "passive"))
      (node (ref "C57") (pin "1") (pinfunction "1_1") (pintype "passive"))
      (node (ref "IC1") (pin "11") (pinfunction "V-_11") (pintype "power_in"))
      (node (ref "IC10") (pin "27") (pinfunction "V-_27") (pintype "power_in"))
      (node (ref "IC2") (pin "11") (pinfunction "V-_11") (pintype "power_in"))
      (node (ref "IC3") (pin "11") (pinfunction "V-_11") (pintype "power_in"))
      (node (ref "IC4") (pin "11") (pinfunction "V-_11") (pintype "power_in"))
      (node (ref "IC5") (pin "11") (pinfunction "V-_11") (pintype "power_in"))
      (node (ref "IC6") (pin "11") (pinfunction "V-_11") (pintype "power_in"))
      (node (ref "IC7") (pin "11") (pinfunction "V-_11") (pintype "power_in"))
      (node (ref "IC8") (pin "11") (pinfunction "V-_11") (pintype "power_in"))
      (node (ref "IC9") (pin "27") (pinfunction "V-_27") (pintype "power_in"))
      (node (ref "IO-AN") (pin "3") (pinfunction "3_3") (pintype "passive"))
      (node (ref "J1") (pin "3") (pinfunction "S_3") (pintype "passive"))
      (node (ref "SV1") (pin "35") (pinfunction "35_35") (pintype "passive"))
    )
    (net (code "81") (name "unconnected-(IC9-NC-Pad2)") (class "Default")
      (node (ref "IC9") (pin "2") (pinfunction "NC_2") (pintype "no_connect"))
    )
    (net (code "82") (name "unconnected-(IC9-NC-Pad3)") (class "Default")
      (node (ref "IC9") (pin "3") (pinfunction "NC_3") (pintype "no_connect"))
    )
    (net (code "83") (name "unconnected-(IC9-NC-Pad13)") (class "Default")
      (node (ref "IC9") (pin "13") (pinfunction "NC_13") (pintype "no_connect"))
    )
    (net (code "84") (name "unconnected-(IC10-NC-Pad2)") (class "Default")
      (node (ref "IC10") (pin "2") (pinfunction "NC_2") (pintype "no_connect"))
    )
    (net (code "85") (name "unconnected-(IC10-NC-Pad3)") (class "Default")
      (node (ref "IC10") (pin "3") (pinfunction "NC_3") (pintype "no_connect"))
    )
    (net (code "86") (name "unconnected-(IC10-NC-Pad13)") (class "Default")
      (node (ref "IC10") (pin "13") (pinfunction "NC_13") (pintype "no_connect"))
    )
    (net (code "87") (name "unconnected-(IO-AN-Pad4)") (class "Default")
      (node (ref "IO-AN") (pin "4") (pinfunction "4_4") (pintype "passive"))
    )
    (net (code "88") (name "unconnected-(SV1-Pad36)") (class "Default")
      (node (ref "SV1") (pin "36") (pinfunction "36_36") (pintype "passive"))
    )
  )
)
